# POWER.net
KiCad netlist of a schematic drawn in Altium Designer
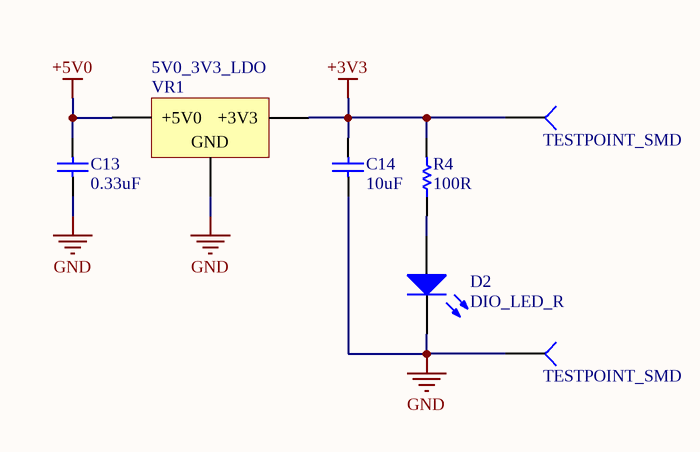
[diagram p0: POWER.SchDoc]

(export (version "E")
  (design (tool "Eeschema 10.0.6"))
  (components
    (comp (ref "C13")
      (value "0.33uF")
      (footprint "CAPC0603(1608)55_N")
      (description "CAP CER 0.33UF 16V X7R 0603")
      (fields
        (field (name "PART NUMBER") "GRM188R71C334KA01D")
        (field (name "MANUFACTURER") "Murata Electronics North America")
      )
      (libsource (lib "UWRT_Schematic_Library_2019") (part "CAP_0.33uF_16V_0603"))
    )
    (comp (ref "C14")
      (value "10uF")
      (footprint "CAPC0603(1608)55_N")
      (description "CAP CER 10UF 10V X5R 0603")
      (fields (field (name "PART NUMBER") "CC0603MRX5R6BB106") (field (name "MANUFACTURER") "Yageo"))
      (libsource (lib "UWRT_Schematic_Library_2019") (part "CAP_10uF_0603"))
    )
    (comp (ref "D2")
      (value "DIO_LED_R")
      (footprint "LED_0805")
      (description "LED RED DIFFUSED 0805 SMD")
      (fields (field (name "PART NUMBER") "LS R976-NR-1") (field (name "MANUFACTURER") "OSRAM"))
      (libsource (lib "UWRT_Schematic_Library_2019") (part "DIO_LED_R"))
    )
    (comp (ref "R4")
      (value "100R")
      (footprint "RESC0603(1608)_N")
      (description "RES SMD 100 OHM 1% 1/10W 0603")
      (fields (field (name "MANUFACTURER") "Yageo") (field (name "TOLERANCE") "1%"))
      (libsource (lib "UWRT_Schematic_Library_2019") (part "RES_100R_0603"))
    )
    (comp (ref "TP3")
      (value "TESTPOINT_SMD")
      (footprint "TESTPOINT")
      (libsource (lib "UWRT_Schematic_Library_2019") (part "TESTPOINT_SMD"))
    )
    (comp (ref "TP4")
      (value "TESTPOINT_SMD")
      (footprint "TESTPOINT")
      (libsource (lib "UWRT_Schematic_Library_2019") (part "TESTPOINT_SMD"))
    )
    (comp (ref "VR1")
      (value "5V0_3V3_LDO")
      (footprint "UWRT_Footprint_Library_2019:VOLTAGE_REGULATOR")
      (description "IC REG LINEAR 3.3V 1A DPAK")
      (fields (field (name "PART NUMBER") "NCP1117DT33T5G") (field (name "MANUFACTURER") "ON Semiconductor"))
      (libsource (lib "UWRT_Schematic_Library_2019") (part "5V0_3V3_LDO"))
    )
  )
  (nets
    (net (code "1") (name "+3V3") (class "Default")
      (node (ref "C14") (pin "2") (pinfunction "2_2") (pintype "passive"))
      (node (ref "R4") (pin "2") (pinfunction "2_2") (pintype "passive"))
      (node (ref "TP3") (pin "1") (pinfunction "=value_1") (pintype "passive"))
      (node (ref "VR1") (pin "3") (pinfunction "+3V3_3") (pintype "passive"))
    )
    (net (code "2") (name "+5V0") (class "Default")
      (node (ref "C13") (pin "2") (pinfunction "2_2") (pintype "passive"))
      (node (ref "VR1") (pin "1") (pinfunction "+5V0_1") (pintype "passive"))
    )
    (net (code "3") (name "GND") (class "Default")
      (node (ref "C13") (pin "1") (pinfunction "1_1") (pintype "passive"))
      (node (ref "C14") (pin "1") (pinfunction "1_1") (pintype "passive"))
      (node (ref "D2") (pin "2") (pinfunction "K_2") (pintype "passive"))
      (node (ref "TP4") (pin "1") (pinfunction "=value_1") (pintype "passive"))
      (node (ref "VR1") (pin "2") (pinfunction "GND_2") (pintype "passive"))
    )
    (net (code "4") (name "Net-(D2-A)") (class "Default")
      (node (ref "D2") (pin "1") (pinfunction "A_1") (pintype "passive"))
      (node (ref "R4") (pin "1") (pinfunction "1_1") (pintype "passive"))
    )
  )
)
